# ATEM_GPI-Tally_Breakout_Board.net
KiCad netlist of a schematic drawn in EAGLE
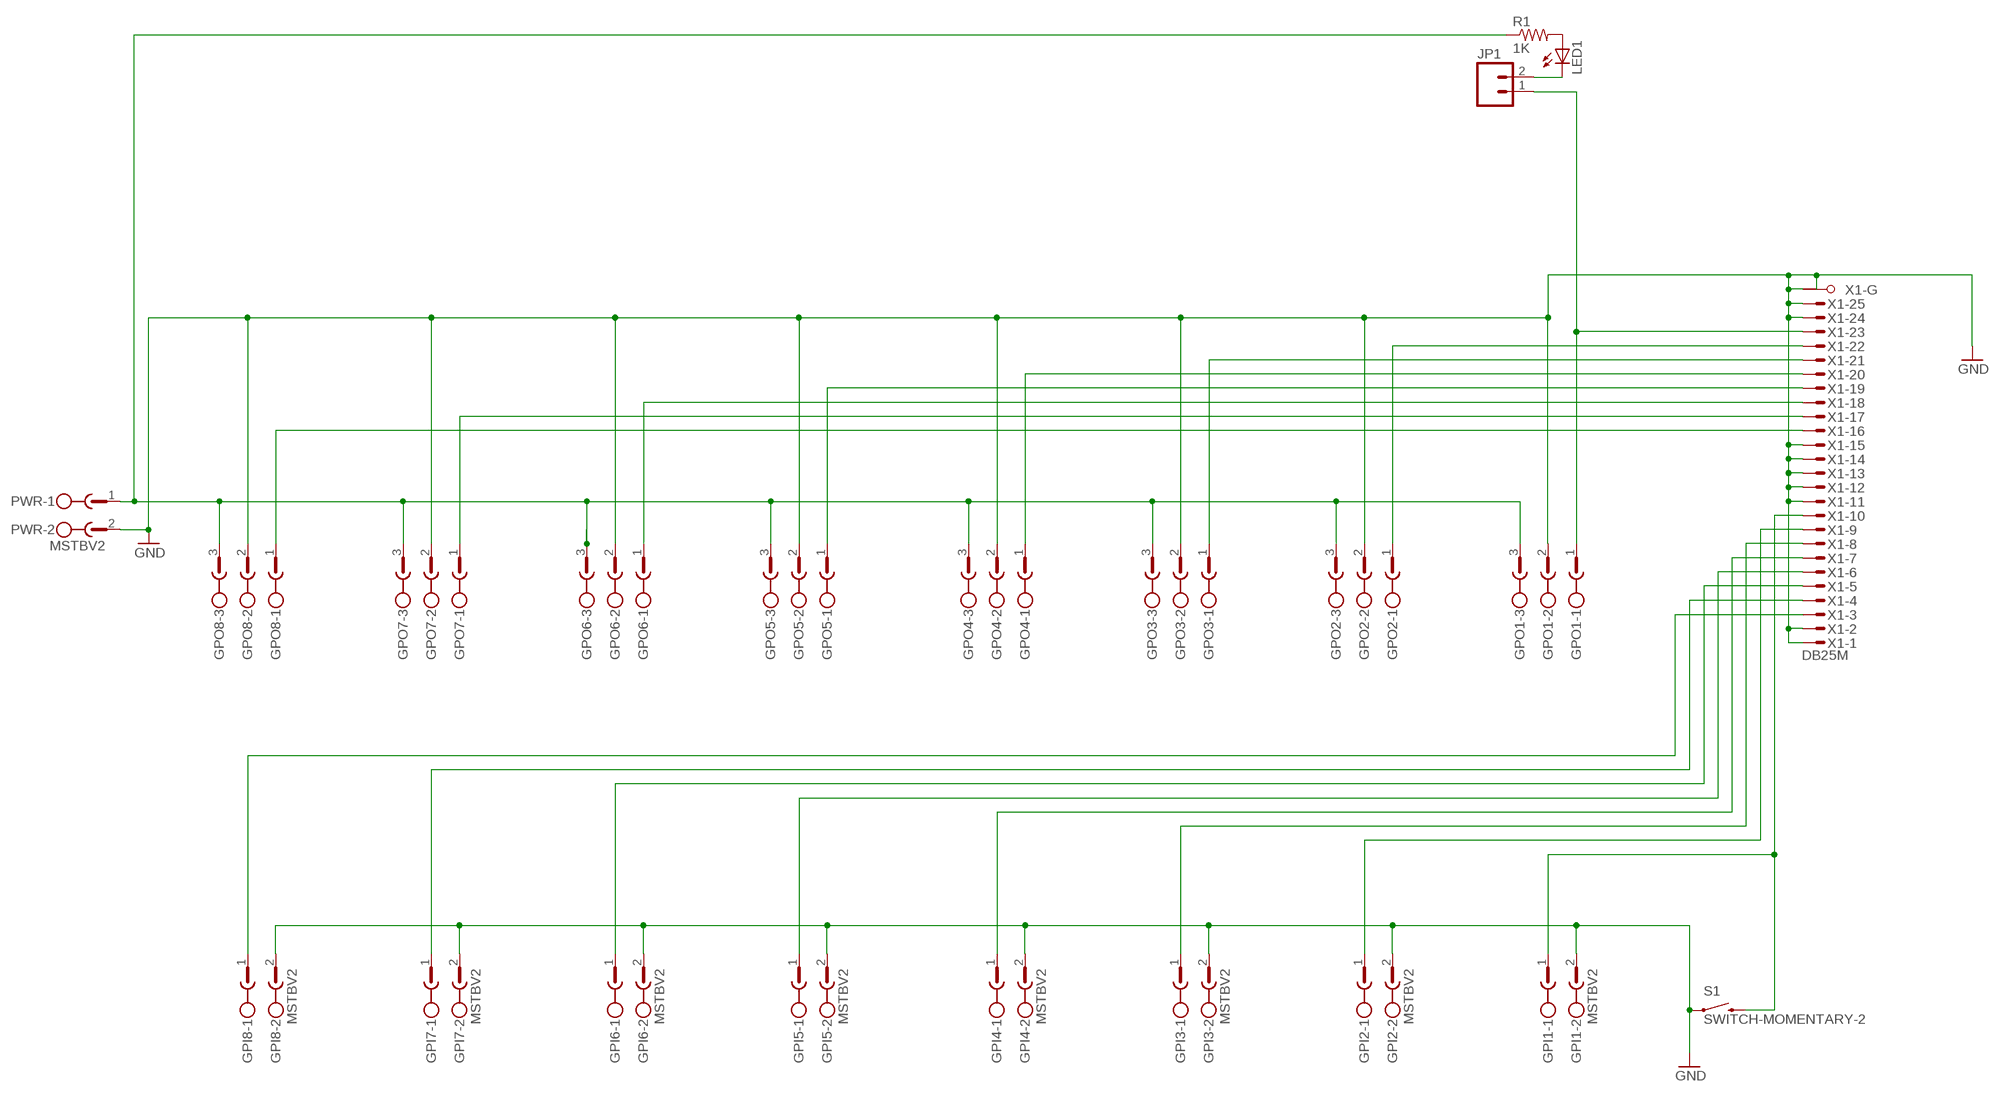
[diagram p0: schematic, sheet 1]

(export (version "E")
  (design (tool "Eeschema 10.0.6"))
  (components
    (comp (ref "GPI1")
      (value "MSTBV2")
      (footprint "eagle-import:MSTBV2")
      (fields
        (field (name "MPN") "MSTBV 2,5/2-GF-5.08")
        (field (name "MPN_1") "MSTBV 2,5/2-GF-5.08")
        (field (name "OC_FARNELL") "1792792")
        (field (name "OC_NEWARK") "69R9845")
      )
      (libsource (lib "eagle-import") (part "MSTBV2"))
    )
    (comp (ref "GPI2")
      (value "MSTBV2")
      (footprint "eagle-import:MSTBV2")
      (fields
        (field (name "MPN") "MSTBV 2,5/2-GF-5.08")
        (field (name "MPN_1") "MSTBV 2,5/2-GF-5.08")
        (field (name "OC_FARNELL") "1792792")
        (field (name "OC_NEWARK") "69R9845")
      )
      (libsource (lib "eagle-import") (part "MSTBV2"))
    )
    (comp (ref "GPI3")
      (value "MSTBV2")
      (footprint "eagle-import:MSTBV2")
      (fields
        (field (name "MPN") "MSTBV 2,5/2-GF-5.08")
        (field (name "MPN_1") "MSTBV 2,5/2-GF-5.08")
        (field (name "OC_FARNELL") "1792792")
        (field (name "OC_NEWARK") "69R9845")
      )
      (libsource (lib "eagle-import") (part "MSTBV2"))
    )
    (comp (ref "GPI4")
      (value "MSTBV2")
      (footprint "eagle-import:MSTBV2")
      (fields
        (field (name "MPN") "MSTBV 2,5/2-GF-5.08")
        (field (name "MPN_1") "MSTBV 2,5/2-GF-5.08")
        (field (name "OC_FARNELL") "1792792")
        (field (name "OC_NEWARK") "69R9845")
      )
      (libsource (lib "eagle-import") (part "MSTBV2"))
    )
    (comp (ref "GPI5")
      (value "MSTBV2")
      (footprint "eagle-import:MSTBV2")
      (fields
        (field (name "MPN") "MSTBV 2,5/2-GF-5.08")
        (field (name "MPN_1") "MSTBV 2,5/2-GF-5.08")
        (field (name "OC_FARNELL") "1792792")
        (field (name "OC_NEWARK") "69R9845")
      )
      (libsource (lib "eagle-import") (part "MSTBV2"))
    )
    (comp (ref "GPI6")
      (value "MSTBV2")
      (footprint "eagle-import:MSTBV2")
      (fields
        (field (name "MPN") "MSTBV 2,5/2-GF-5.08")
        (field (name "MPN_1") "MSTBV 2,5/2-GF-5.08")
        (field (name "OC_FARNELL") "1792792")
        (field (name "OC_NEWARK") "69R9845")
      )
      (libsource (lib "eagle-import") (part "MSTBV2"))
    )
    (comp (ref "GPI7")
      (value "MSTBV2")
      (footprint "eagle-import:MSTBV2")
      (fields
        (field (name "MPN") "MSTBV 2,5/2-GF-5.08")
        (field (name "MPN_1") "MSTBV 2,5/2-GF-5.08")
        (field (name "OC_FARNELL") "1792792")
        (field (name "OC_NEWARK") "69R9845")
      )
      (libsource (lib "eagle-import") (part "MSTBV2"))
    )
    (comp (ref "GPI8")
      (value "MSTBV2")
      (footprint "eagle-import:MSTBV2")
      (fields
        (field (name "MPN") "MSTBV 2,5/2-GF-5.08")
        (field (name "MPN_1") "MSTBV 2,5/2-GF-5.08")
        (field (name "OC_FARNELL") "1792792")
        (field (name "OC_NEWARK") "69R9845")
      )
      (libsource (lib "eagle-import") (part "MSTBV2"))
    )
    (comp (ref "GPO1")
      (value "CON1")
      (footprint "eagle-import:MSTBV3")
      (fields (field (name "MPN") "MSTBV 2,5/3-GF-5.08"))
      (libsource (lib "eagle-import") (part "MSTBV3"))
    )
    (comp (ref "GPO2")
      (value "CON1")
      (footprint "eagle-import:MSTBV3")
      (fields (field (name "MPN") "MSTBV 2,5/3-GF-5.08"))
      (libsource (lib "eagle-import") (part "MSTBV3"))
    )
    (comp (ref "GPO3")
      (value "CON1")
      (footprint "eagle-import:MSTBV3")
      (fields (field (name "MPN") "MSTBV 2,5/3-GF-5.08"))
      (libsource (lib "eagle-import") (part "MSTBV3"))
    )
    (comp (ref "GPO4")
      (value "CON1")
      (footprint "eagle-import:MSTBV3")
      (fields (field (name "MPN") "MSTBV 2,5/3-GF-5.08"))
      (libsource (lib "eagle-import") (part "MSTBV3"))
    )
    (comp (ref "GPO5")
      (value "CON1")
      (footprint "eagle-import:MSTBV3")
      (fields (field (name "MPN") "MSTBV 2,5/3-GF-5.08"))
      (libsource (lib "eagle-import") (part "MSTBV3"))
    )
    (comp (ref "GPO6")
      (value "CON1")
      (footprint "eagle-import:MSTBV3")
      (fields (field (name "MPN") "MSTBV 2,5/3-GF-5.08"))
      (libsource (lib "eagle-import") (part "MSTBV3"))
    )
    (comp (ref "GPO7")
      (value "CON1")
      (footprint "eagle-import:MSTBV3")
      (fields (field (name "MPN") "MSTBV 2,5/3-GF-5.08"))
      (libsource (lib "eagle-import") (part "MSTBV3"))
    )
    (comp (ref "GPO8")
      (value "CON1")
      (footprint "eagle-import:MSTBV3")
      (fields (field (name "MPN") "MSTBV 2,5/3-GF-5.08"))
      (libsource (lib "eagle-import") (part "MSTBV3"))
    )
    (comp (ref "JP1")
      (value "M02LOCK")
      (footprint "eagle-import:1X02_LOCK")
      (libsource (lib "eagle-import") (part "M02LOCK"))
    )
    (comp (ref "LED1")
      (value "LED5MM")
      (footprint "eagle-import:LED5MM")
      (libsource (lib "eagle-import") (part "LED5MM"))
    )
    (comp (ref "PWR")
      (value "MSTBV2")
      (footprint "eagle-import:MSTBV2")
      (fields (field (name "MPN") "MSTBV 2,5/2-GF-5.08"))
      (libsource (lib "eagle-import") (part "MSTBV2"))
    )
    (comp (ref "R1")
      (value "1K")
      (footprint "eagle-import:AXIAL-0.4")
      (libsource (lib "eagle-import") (part "RESISTORPTH-1/4W"))
    )
    (comp (ref "S1")
      (value "SWITCH-MOMENTARY-2")
      (footprint "eagle-import:TACTILE_SWITCH_TALL")
      (libsource (lib "eagle-import") (part "SWITCH-MOMENTARY-2"))
    )
    (comp (ref "X1")
      (value "DB25M")
      (footprint "eagle-import:M25HP")
      (libsource (lib "eagle-import") (part "M25HPS"))
    )
  )
  (nets
    (net (code "1") (name "GND") (class "Default")
      (node (ref "GPI1") (pin "2") (pinfunction "1_2") (pintype "passive"))
      (node (ref "GPI2") (pin "2") (pinfunction "1_2") (pintype "passive"))
      (node (ref "GPI3") (pin "2") (pinfunction "1_2") (pintype "passive"))
      (node (ref "GPI4") (pin "2") (pinfunction "1_2") (pintype "passive"))
      (node (ref "GPI5") (pin "2") (pinfunction "1_2") (pintype "passive"))
      (node (ref "GPI6") (pin "2") (pinfunction "1_2") (pintype "passive"))
      (node (ref "GPI7") (pin "2") (pinfunction "1_2") (pintype "passive"))
      (node (ref "GPI8") (pin "2") (pinfunction "1_2") (pintype "passive"))
      (node (ref "GPO1") (pin "2") (pinfunction "1_2") (pintype "passive"))
      (node (ref "GPO2") (pin "2") (pinfunction "1_2") (pintype "passive"))
      (node (ref "GPO3") (pin "2") (pinfunction "1_2") (pintype "passive"))
      (node (ref "GPO4") (pin "2") (pinfunction "1_2") (pintype "passive"))
      (node (ref "GPO5") (pin "2") (pinfunction "1_2") (pintype "passive"))
      (node (ref "GPO6") (pin "2") (pinfunction "1_2") (pintype "passive"))
      (node (ref "GPO7") (pin "2") (pinfunction "1_2") (pintype "passive"))
      (node (ref "GPO8") (pin "2") (pinfunction "1_2") (pintype "passive"))
      (node (ref "PWR") (pin "2") (pinfunction "1_2") (pintype "passive"))
      (node (ref "S1") (pin "A2") (pinfunction "1_A2") (pintype "passive"))
      (node (ref "X1") (pin "1") (pinfunction "M_1") (pintype "passive"))
      (node (ref "X1") (pin "11") (pinfunction "M_11") (pintype "passive"))
      (node (ref "X1") (pin "12") (pinfunction "M_12") (pintype "passive"))
      (node (ref "X1") (pin "13") (pinfunction "M_13") (pintype "passive"))
      (node (ref "X1") (pin "14") (pinfunction "M_14") (pintype "passive"))
      (node (ref "X1") (pin "15") (pinfunction "M_15") (pintype "passive"))
      (node (ref "X1") (pin "2") (pinfunction "M_2") (pintype "passive"))
      (node (ref "X1") (pin "24") (pinfunction "M_24") (pintype "passive"))
      (node (ref "X1") (pin "25") (pinfunction "M_25") (pintype "passive"))
      (node (ref "X1") (pin "G1") (pinfunction "G1_G1") (pintype "passive"))
      (node (ref "X1") (pin "G2") (pinfunction "G2_G2") (pintype "passive"))
    )
    (net (code "2") (name "Net-(GPO1C-1)") (class "Default")
      (node (ref "GPO1") (pin "3") (pinfunction "1_3") (pintype "passive"))
      (node (ref "GPO2") (pin "3") (pinfunction "1_3") (pintype "passive"))
      (node (ref "GPO3") (pin "3") (pinfunction "1_3") (pintype "passive"))
      (node (ref "GPO4") (pin "3") (pinfunction "1_3") (pintype "passive"))
      (node (ref "GPO5") (pin "3") (pinfunction "1_3") (pintype "passive"))
      (node (ref "GPO6") (pin "3") (pinfunction "1_3") (pintype "passive"))
      (node (ref "GPO7") (pin "3") (pinfunction "1_3") (pintype "passive"))
      (node (ref "GPO8") (pin "3") (pinfunction "1_3") (pintype "passive"))
      (node (ref "PWR") (pin "1") (pinfunction "1_1") (pintype "passive"))
      (node (ref "R1") (pin "P$1") (pinfunction "1_P$1") (pintype "passive"))
    )
    (net (code "3") (name "Net-(LED1-C)") (class "Default")
      (node (ref "JP1") (pin "2") (pinfunction "2_2") (pintype "passive"))
      (node (ref "LED1") (pin "K") (pinfunction "C_K") (pintype "passive"))
    )
    (net (code "4") (name "Net-(R1-2)") (class "Default")
      (node (ref "LED1") (pin "A") (pinfunction "A_A") (pintype "passive"))
      (node (ref "R1") (pin "P$2") (pinfunction "2_P$2") (pintype "passive"))
    )
    (net (code "5") (name "Net-(S1-2)") (class "Default")
      (node (ref "GPI1") (pin "1") (pinfunction "1_1") (pintype "passive"))
      (node (ref "S1") (pin "B2") (pinfunction "2_B2") (pintype "passive"))
      (node (ref "X1") (pin "10") (pinfunction "M_10") (pintype "passive"))
    )
    (net (code "6") (name "Net-(X1H-M)") (class "Default")
      (node (ref "GPO8") (pin "1") (pinfunction "1_1") (pintype "passive"))
      (node (ref "X1") (pin "16") (pinfunction "M_16") (pintype "passive"))
    )
    (net (code "7") (name "Net-(X1I-M)") (class "Default")
      (node (ref "GPO7") (pin "1") (pinfunction "1_1") (pintype "passive"))
      (node (ref "X1") (pin "17") (pinfunction "M_17") (pintype "passive"))
    )
    (net (code "8") (name "Net-(X1J-M)") (class "Default")
      (node (ref "GPO6") (pin "1") (pinfunction "1_1") (pintype "passive"))
      (node (ref "X1") (pin "18") (pinfunction "M_18") (pintype "passive"))
    )
    (net (code "9") (name "Net-(X1K-M)") (class "Default")
      (node (ref "GPO5") (pin "1") (pinfunction "1_1") (pintype "passive"))
      (node (ref "X1") (pin "19") (pinfunction "M_19") (pintype "passive"))
    )
    (net (code "10") (name "Net-(X1M-M)") (class "Default")
      (node (ref "GPO4") (pin "1") (pinfunction "1_1") (pintype "passive"))
      (node (ref "X1") (pin "20") (pinfunction "M_20") (pintype "passive"))
    )
    (net (code "11") (name "Net-(X1N-M)") (class "Default")
      (node (ref "GPO3") (pin "1") (pinfunction "1_1") (pintype "passive"))
      (node (ref "X1") (pin "21") (pinfunction "M_21") (pintype "passive"))
    )
    (net (code "12") (name "Net-(X1O-M)") (class "Default")
      (node (ref "GPO2") (pin "1") (pinfunction "1_1") (pintype "passive"))
      (node (ref "X1") (pin "22") (pinfunction "M_22") (pintype "passive"))
    )
    (net (code "13") (name "Net-(X1P-M)") (class "Default")
      (node (ref "GPO1") (pin "1") (pinfunction "1_1") (pintype "passive"))
      (node (ref "JP1") (pin "1") (pinfunction "1_1") (pintype "passive"))
      (node (ref "X1") (pin "23") (pinfunction "M_23") (pintype "passive"))
    )
    (net (code "14") (name "Net-(X1S-M)") (class "Default")
      (node (ref "GPI8") (pin "1") (pinfunction "1_1") (pintype "passive"))
      (node (ref "X1") (pin "3") (pinfunction "M_3") (pintype "passive"))
    )
    (net (code "15") (name "Net-(X1T-M)") (class "Default")
      (node (ref "GPI7") (pin "1") (pinfunction "1_1") (pintype "passive"))
      (node (ref "X1") (pin "4") (pinfunction "M_4") (pintype "passive"))
    )
    (net (code "16") (name "Net-(X1U-M)") (class "Default")
      (node (ref "GPI6") (pin "1") (pinfunction "1_1") (pintype "passive"))
      (node (ref "X1") (pin "5") (pinfunction "M_5") (pintype "passive"))
    )
    (net (code "17") (name "Net-(X1V-M)") (class "Default")
      (node (ref "GPI5") (pin "1") (pinfunction "1_1") (pintype "passive"))
      (node (ref "X1") (pin "6") (pinfunction "M_6") (pintype "passive"))
    )
    (net (code "18") (name "Net-(X1W-M)") (class "Default")
      (node (ref "GPI4") (pin "1") (pinfunction "1_1") (pintype "passive"))
      (node (ref "X1") (pin "7") (pinfunction "M_7") (pintype "passive"))
    )
    (net (code "19") (name "Net-(X1X-M)") (class "Default")
      (node (ref "GPI3") (pin "1") (pinfunction "1_1") (pintype "passive"))
      (node (ref "X1") (pin "8") (pinfunction "M_8") (pintype "passive"))
    )
    (net (code "20") (name "Net-(X1Y-M)") (class "Default")
      (node (ref "GPI2") (pin "1") (pinfunction "1_1") (pintype "passive"))
      (node (ref "X1") (pin "9") (pinfunction "M_9") (pintype "passive"))
    )
  )
)
